# EHDD_LAB_1.net
KiCad netlist of a schematic drawn in EAGLE
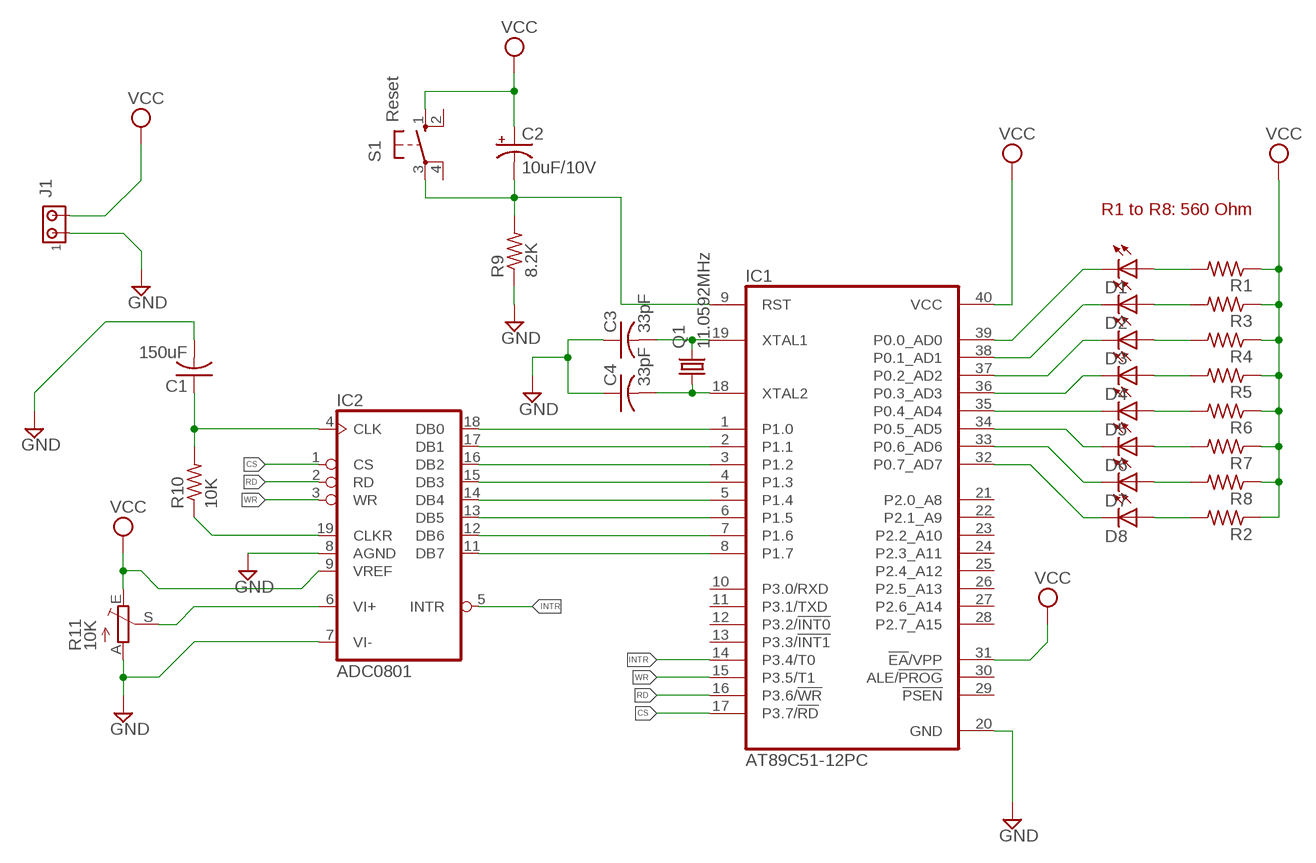
[diagram p0: schematic, sheet 1]

(export (version "E")
  (design (tool "Eeschema 10.0.6"))
  (components
    (comp (ref "C1")
      (value "150uF")
      (footprint "eagle-import:C025-025X050")
      (libsource (lib "eagle-import") (part "C-US025-025X050"))
    )
    (comp (ref "C2")
      (value "10uF/10V")
      (footprint "eagle-import:E2,5-5")
      (libsource (lib "eagle-import") (part "CPOL-USE2.5-5"))
    )
    (comp (ref "C3")
      (value "33pF")
      (footprint "eagle-import:C025-025X050")
      (libsource (lib "eagle-import") (part "C-US025-025X050"))
    )
    (comp (ref "C4")
      (value "33pF")
      (footprint "eagle-import:C025-025X050")
      (libsource (lib "eagle-import") (part "C-US025-025X050"))
    )
    (comp (ref "D1")
      (value "LEDCHIPLED_0805")
      (footprint "eagle-import:CHIPLED_0805")
      (libsource (lib "eagle-import") (part "LEDCHIPLED_0805"))
    )
    (comp (ref "D2")
      (value "LEDCHIPLED_0805")
      (footprint "eagle-import:CHIPLED_0805")
      (libsource (lib "eagle-import") (part "LEDCHIPLED_0805"))
    )
    (comp (ref "D3")
      (value "LEDCHIPLED_0805")
      (footprint "eagle-import:CHIPLED_0805")
      (libsource (lib "eagle-import") (part "LEDCHIPLED_0805"))
    )
    (comp (ref "D4")
      (value "LEDCHIPLED_0805")
      (footprint "eagle-import:CHIPLED_0805")
      (libsource (lib "eagle-import") (part "LEDCHIPLED_0805"))
    )
    (comp (ref "D5")
      (value "LEDCHIPLED_0805")
      (footprint "eagle-import:CHIPLED_0805")
      (libsource (lib "eagle-import") (part "LEDCHIPLED_0805"))
    )
    (comp (ref "D6")
      (value "LEDCHIPLED_0805")
      (footprint "eagle-import:CHIPLED_0805")
      (libsource (lib "eagle-import") (part "LEDCHIPLED_0805"))
    )
    (comp (ref "D7")
      (value "LEDCHIPLED_0805")
      (footprint "eagle-import:CHIPLED_0805")
      (libsource (lib "eagle-import") (part "LEDCHIPLED_0805"))
    )
    (comp (ref "D8")
      (value "LEDCHIPLED_0805")
      (footprint "eagle-import:CHIPLED_0805")
      (libsource (lib "eagle-import") (part "LEDCHIPLED_0805"))
    )
    (comp (ref "IC1")
      (value "AT89C51-12PC")
      (footprint "eagle-import:DIL40")
      (libsource (lib "eagle-import") (part "AT89C51-PC12"))
    )
    (comp (ref "IC2")
      (value "ADC0801")
      (footprint "eagle-import:DIL20")
      (libsource (lib "eagle-import") (part "ADC0801"))
    )
    (comp (ref "J1")
      (value "MTA02-100")
      (footprint "eagle-import:10X02MTA")
      (libsource (lib "eagle-import") (part "MTA02-100"))
    )
    (comp (ref "Q1")
      (value "11.0592MHz")
      (footprint "eagle-import:TC26H")
      (libsource (lib "eagle-import") (part "CRYSTALTC26H"))
    )
    (comp (ref "R1")
      (value "R-US_R2512")
      (footprint "eagle-import:R2512")
      (libsource (lib "eagle-import") (part "R-US_R2512"))
    )
    (comp (ref "R2")
      (value "R-US_R2512")
      (footprint "eagle-import:R2512")
      (libsource (lib "eagle-import") (part "R-US_R2512"))
    )
    (comp (ref "R3")
      (value "R-US_R2512")
      (footprint "eagle-import:R2512")
      (libsource (lib "eagle-import") (part "R-US_R2512"))
    )
    (comp (ref "R4")
      (value "R-US_R2512")
      (footprint "eagle-import:R2512")
      (libsource (lib "eagle-import") (part "R-US_R2512"))
    )
    (comp (ref "R5")
      (value "R-US_R2512")
      (footprint "eagle-import:R2512")
      (libsource (lib "eagle-import") (part "R-US_R2512"))
    )
    (comp (ref "R6")
      (value "R-US_R2512")
      (footprint "eagle-import:R2512")
      (libsource (lib "eagle-import") (part "R-US_R2512"))
    )
    (comp (ref "R7")
      (value "R-US_R2512")
      (footprint "eagle-import:R2512")
      (libsource (lib "eagle-import") (part "R-US_R2512"))
    )
    (comp (ref "R8")
      (value "R-US_R2512")
      (footprint "eagle-import:R2512")
      (libsource (lib "eagle-import") (part "R-US_R2512"))
    )
    (comp (ref "R9")
      (value "8.2K")
      (footprint "eagle-import:R2512")
      (libsource (lib "eagle-import") (part "R-US_R2512"))
    )
    (comp (ref "R10")
      (value "10K")
      (footprint "eagle-import:R2512")
      (libsource (lib "eagle-import") (part "R-US_R2512"))
    )
    (comp (ref "R11")
      (value "10K")
      (footprint "eagle-import:B25U")
      (libsource (lib "eagle-import") (part "TRIM_EU-B25U"))
    )
    (comp (ref "S1")
      (value "Reset")
      (footprint "eagle-import:B3F-10XX")
      (fields (field (name "MPN") "B3F-1000"))
      (libsource (lib "eagle-import") (part "10-XX"))
    )
  )
  (nets
    (net (code "1") (name "CS") (class "Default")
      (node (ref "IC1") (pin "17") (pinfunction "P3.7/~{RD}_17") (pintype "bidirectional"))
      (node (ref "IC2") (pin "1") (pinfunction "CS_1") (pintype "input"))
    )
    (net (code "2") (name "GND") (class "Default")
      (node (ref "C1") (pin "2") (pinfunction "2_2") (pintype "passive"))
      (node (ref "C3") (pin "1") (pinfunction "1_1") (pintype "passive"))
      (node (ref "C4") (pin "1") (pinfunction "1_1") (pintype "passive"))
      (node (ref "IC1") (pin "20") (pinfunction "GND_20") (pintype "power_in"))
      (node (ref "IC2") (pin "7") (pinfunction "VI-_7") (pintype "input"))
      (node (ref "IC2") (pin "8") (pinfunction "AGND_8") (pintype "input"))
      (node (ref "J1") (pin "1") (pinfunction "1_1") (pintype "passive"))
      (node (ref "R11") (pin "A") (pinfunction "A_A") (pintype "passive"))
      (node (ref "R9") (pin "1") (pinfunction "1_1") (pintype "passive"))
    )
    (net (code "3") (name "INTR") (class "Default")
      (node (ref "IC1") (pin "14") (pinfunction "P3.4/T0_14") (pintype "bidirectional"))
      (node (ref "IC2") (pin "5") (pinfunction "INTR_5") (pintype "output"))
    )
    (net (code "4") (name "Net-(D1-PadA)") (class "Default")
      (node (ref "D1") (pin "A") (pinfunction "A_A") (pintype "passive"))
      (node (ref "R1") (pin "2") (pinfunction "2_2") (pintype "passive"))
    )
    (net (code "5") (name "Net-(D2-PadA)") (class "Default")
      (node (ref "D2") (pin "A") (pinfunction "A_A") (pintype "passive"))
      (node (ref "R3") (pin "2") (pinfunction "2_2") (pintype "passive"))
    )
    (net (code "6") (name "Net-(D3-PadA)") (class "Default")
      (node (ref "D3") (pin "A") (pinfunction "A_A") (pintype "passive"))
      (node (ref "R4") (pin "2") (pinfunction "2_2") (pintype "passive"))
    )
    (net (code "7") (name "Net-(D4-PadA)") (class "Default")
      (node (ref "D4") (pin "A") (pinfunction "A_A") (pintype "passive"))
      (node (ref "R5") (pin "2") (pinfunction "2_2") (pintype "passive"))
    )
    (net (code "8") (name "Net-(D5-PadA)") (class "Default")
      (node (ref "D5") (pin "A") (pinfunction "A_A") (pintype "passive"))
      (node (ref "R6") (pin "2") (pinfunction "2_2") (pintype "passive"))
    )
    (net (code "9") (name "Net-(D6-PadA)") (class "Default")
      (node (ref "D6") (pin "A") (pinfunction "A_A") (pintype "passive"))
      (node (ref "R7") (pin "2") (pinfunction "2_2") (pintype "passive"))
    )
    (net (code "10") (name "Net-(D7-PadA)") (class "Default")
      (node (ref "D7") (pin "A") (pinfunction "A_A") (pintype "passive"))
      (node (ref "R8") (pin "2") (pinfunction "2_2") (pintype "passive"))
    )
    (net (code "11") (name "Net-(D8-PadA)") (class "Default")
      (node (ref "D8") (pin "A") (pinfunction "A_A") (pintype "passive"))
      (node (ref "R2") (pin "2") (pinfunction "2_2") (pintype "passive"))
    )
    (net (code "12") (name "Net-(IC1-P0.0_AD0)") (class "Default")
      (node (ref "D1") (pin "C") (pinfunction "C_C") (pintype "passive"))
      (node (ref "IC1") (pin "39") (pinfunction "P0.0_AD0_39") (pintype "bidirectional"))
    )
    (net (code "13") (name "Net-(IC1-P0.1_AD1)") (class "Default")
      (node (ref "D2") (pin "C") (pinfunction "C_C") (pintype "passive"))
      (node (ref "IC1") (pin "38") (pinfunction "P0.1_AD1_38") (pintype "bidirectional"))
    )
    (net (code "14") (name "Net-(IC1-P0.2_AD2)") (class "Default")
      (node (ref "D3") (pin "C") (pinfunction "C_C") (pintype "passive"))
      (node (ref "IC1") (pin "37") (pinfunction "P0.2_AD2_37") (pintype "bidirectional"))
    )
    (net (code "15") (name "Net-(IC1-P0.3_AD3)") (class "Default")
      (node (ref "D4") (pin "C") (pinfunction "C_C") (pintype "passive"))
      (node (ref "IC1") (pin "36") (pinfunction "P0.3_AD3_36") (pintype "bidirectional"))
    )
    (net (code "16") (name "Net-(IC1-P0.4_AD4)") (class "Default")
      (node (ref "D5") (pin "C") (pinfunction "C_C") (pintype "passive"))
      (node (ref "IC1") (pin "35") (pinfunction "P0.4_AD4_35") (pintype "bidirectional"))
    )
    (net (code "17") (name "Net-(IC1-P0.5_AD5)") (class "Default")
      (node (ref "D6") (pin "C") (pinfunction "C_C") (pintype "passive"))
      (node (ref "IC1") (pin "34") (pinfunction "P0.5_AD5_34") (pintype "bidirectional"))
    )
    (net (code "18") (name "Net-(IC1-P0.6_AD6)") (class "Default")
      (node (ref "D7") (pin "C") (pinfunction "C_C") (pintype "passive"))
      (node (ref "IC1") (pin "33") (pinfunction "P0.6_AD6_33") (pintype "bidirectional"))
    )
    (net (code "19") (name "Net-(IC1-P0.7_AD7)") (class "Default")
      (node (ref "D8") (pin "C") (pinfunction "C_C") (pintype "passive"))
      (node (ref "IC1") (pin "32") (pinfunction "P0.7_AD7_32") (pintype "bidirectional"))
    )
    (net (code "20") (name "Net-(IC1-P1.0)") (class "Default")
      (node (ref "IC1") (pin "1") (pinfunction "P1.0_1") (pintype "bidirectional"))
      (node (ref "IC2") (pin "18") (pinfunction "DB0_18") (pintype "output"))
    )
    (net (code "21") (name "Net-(IC1-P1.1)") (class "Default")
      (node (ref "IC1") (pin "2") (pinfunction "P1.1_2") (pintype "bidirectional"))
      (node (ref "IC2") (pin "17") (pinfunction "DB1_17") (pintype "output"))
    )
    (net (code "22") (name "Net-(IC1-P1.2)") (class "Default")
      (node (ref "IC1") (pin "3") (pinfunction "P1.2_3") (pintype "bidirectional"))
      (node (ref "IC2") (pin "16") (pinfunction "DB2_16") (pintype "output"))
    )
    (net (code "23") (name "Net-(IC1-P1.3)") (class "Default")
      (node (ref "IC1") (pin "4") (pinfunction "P1.3_4") (pintype "bidirectional"))
      (node (ref "IC2") (pin "15") (pinfunction "DB3_15") (pintype "output"))
    )
    (net (code "24") (name "Net-(IC1-P1.4)") (class "Default")
      (node (ref "IC1") (pin "5") (pinfunction "P1.4_5") (pintype "bidirectional"))
      (node (ref "IC2") (pin "14") (pinfunction "DB4_14") (pintype "output"))
    )
    (net (code "25") (name "Net-(IC1-P1.5)") (class "Default")
      (node (ref "IC1") (pin "6") (pinfunction "P1.5_6") (pintype "bidirectional"))
      (node (ref "IC2") (pin "13") (pinfunction "DB5_13") (pintype "output"))
    )
    (net (code "26") (name "Net-(IC1-P1.6)") (class "Default")
      (node (ref "IC1") (pin "7") (pinfunction "P1.6_7") (pintype "bidirectional"))
      (node (ref "IC2") (pin "12") (pinfunction "DB6_12") (pintype "output"))
    )
    (net (code "27") (name "Net-(IC1-P1.7)") (class "Default")
      (node (ref "IC1") (pin "8") (pinfunction "P1.7_8") (pintype "bidirectional"))
      (node (ref "IC2") (pin "11") (pinfunction "DB7_11") (pintype "output"))
    )
    (net (code "28") (name "Net-(IC1-RST)") (class "Default")
      (node (ref "C2") (pin "-") (pinfunction "-_-") (pintype "passive"))
      (node (ref "IC1") (pin "9") (pinfunction "RST_9") (pintype "input"))
      (node (ref "R9") (pin "2") (pinfunction "2_2") (pintype "passive"))
      (node (ref "S1") (pin "3") (pinfunction "P_3") (pintype "passive"))
    )
    (net (code "29") (name "Net-(IC1-XTAL1)") (class "Default")
      (node (ref "C3") (pin "2") (pinfunction "2_2") (pintype "passive"))
      (node (ref "IC1") (pin "19") (pinfunction "XTAL1_19") (pintype "input"))
      (node (ref "Q1") (pin "2") (pinfunction "2_2") (pintype "passive"))
    )
    (net (code "30") (name "Net-(IC1-XTAL2)") (class "Default")
      (node (ref "C4") (pin "2") (pinfunction "2_2") (pintype "passive"))
      (node (ref "IC1") (pin "18") (pinfunction "XTAL2_18") (pintype "input"))
      (node (ref "Q1") (pin "1") (pinfunction "1_1") (pintype "passive"))
    )
    (net (code "31") (name "Net-(IC2A-CLK)") (class "Default")
      (node (ref "C1") (pin "1") (pinfunction "1_1") (pintype "passive"))
      (node (ref "IC2") (pin "4") (pinfunction "CLK_4") (pintype "input"))
      (node (ref "R10") (pin "2") (pinfunction "2_2") (pintype "passive"))
    )
    (net (code "32") (name "Net-(IC2A-CLKR)") (class "Default")
      (node (ref "IC2") (pin "19") (pinfunction "CLKR_19") (pintype "input"))
      (node (ref "R10") (pin "1") (pinfunction "1_1") (pintype "passive"))
    )
    (net (code "33") (name "Net-(IC2A-VI+)") (class "Default")
      (node (ref "IC2") (pin "6") (pinfunction "VI+_6") (pintype "input"))
      (node (ref "R11") (pin "S") (pinfunction "S_S") (pintype "passive"))
    )
    (net (code "34") (name "RD") (class "Default")
      (node (ref "IC1") (pin "16") (pinfunction "P3.6/~{WR}_16") (pintype "bidirectional"))
      (node (ref "IC2") (pin "2") (pinfunction "RD_2") (pintype "input"))
    )
    (net (code "35") (name "VCC") (class "Default")
      (node (ref "C2") (pin "+") (pinfunction "+_+") (pintype "passive"))
      (node (ref "IC1") (pin "31") (pinfunction "~{EA}/VPP_31") (pintype "input"))
      (node (ref "IC1") (pin "40") (pinfunction "VCC_40") (pintype "power_in"))
      (node (ref "IC2") (pin "9") (pinfunction "VREF_9") (pintype "input"))
      (node (ref "J1") (pin "2") (pinfunction "2_2") (pintype "passive"))
      (node (ref "R1") (pin "1") (pinfunction "1_1") (pintype "passive"))
      (node (ref "R11") (pin "E") (pinfunction "E_E") (pintype "passive"))
      (node (ref "R2") (pin "1") (pinfunction "1_1") (pintype "passive"))
      (node (ref "R3") (pin "1") (pinfunction "1_1") (pintype "passive"))
      (node (ref "R4") (pin "1") (pinfunction "1_1") (pintype "passive"))
      (node (ref "R5") (pin "1") (pinfunction "1_1") (pintype "passive"))
      (node (ref "R6") (pin "1") (pinfunction "1_1") (pintype "passive"))
      (node (ref "R7") (pin "1") (pinfunction "1_1") (pintype "passive"))
      (node (ref "R8") (pin "1") (pinfunction "1_1") (pintype "passive"))
      (node (ref "S1") (pin "1") (pinfunction "S_1") (pintype "passive"))
    )
    (net (code "36") (name "WR") (class "Default")
      (node (ref "IC1") (pin "15") (pinfunction "P3.5/T1_15") (pintype "bidirectional"))
      (node (ref "IC2") (pin "3") (pinfunction "WR_3") (pintype "input"))
    )
    (net (code "37") (name "unconnected-(IC1-ALE{slash}~{PROG}-Pad30)") (class "Default")
      (node (ref "IC1") (pin "30") (pinfunction "ALE/~{PROG}_30") (pintype "output"))
    )
    (net (code "38") (name "unconnected-(IC1-P2.0_A8-Pad21)") (class "Default")
      (node (ref "IC1") (pin "21") (pinfunction "P2.0_A8_21") (pintype "bidirectional"))
    )
    (net (code "39") (name "unconnected-(IC1-P2.1_A9-Pad22)") (class "Default")
      (node (ref "IC1") (pin "22") (pinfunction "P2.1_A9_22") (pintype "bidirectional"))
    )
    (net (code "40") (name "unconnected-(IC1-P2.2_A10-Pad23)") (class "Default")
      (node (ref "IC1") (pin "23") (pinfunction "P2.2_A10_23") (pintype "bidirectional"))
    )
    (net (code "41") (name "unconnected-(IC1-P2.3_A11-Pad24)") (class "Default")
      (node (ref "IC1") (pin "24") (pinfunction "P2.3_A11_24") (pintype "bidirectional"))
    )
    (net (code "42") (name "unconnected-(IC1-P2.4_A12-Pad25)") (class "Default")
      (node (ref "IC1") (pin "25") (pinfunction "P2.4_A12_25") (pintype "bidirectional"))
    )
    (net (code "43") (name "unconnected-(IC1-P2.5_A13-Pad26)") (class "Default")
      (node (ref "IC1") (pin "26") (pinfunction "P2.5_A13_26") (pintype "bidirectional"))
    )
    (net (code "44") (name "unconnected-(IC1-P2.6_A14-Pad27)") (class "Default")
      (node (ref "IC1") (pin "27") (pinfunction "P2.6_A14_27") (pintype "bidirectional"))
    )
    (net (code "45") (name "unconnected-(IC1-P2.7_A15-Pad28)") (class "Default")
      (node (ref "IC1") (pin "28") (pinfunction "P2.7_A15_28") (pintype "bidirectional"))
    )
    (net (code "46") (name "unconnected-(IC1-P3.0{slash}RXD-Pad10)") (class "Default")
      (node (ref "IC1") (pin "10") (pinfunction "P3.0/RXD_10") (pintype "bidirectional"))
    )
    (net (code "47") (name "unconnected-(IC1-P3.1{slash}TXD-Pad11)") (class "Default")
      (node (ref "IC1") (pin "11") (pinfunction "P3.1/TXD_11") (pintype "bidirectional"))
    )
    (net (code "48") (name "unconnected-(IC1-P3.2{slash}~{INT0}-Pad12)") (class "Default")
      (node (ref "IC1") (pin "12") (pinfunction "P3.2/~{INT0}_12") (pintype "bidirectional"))
    )
    (net (code "49") (name "unconnected-(IC1-P3.3{slash}~{INT1}-Pad13)") (class "Default")
      (node (ref "IC1") (pin "13") (pinfunction "P3.3/~{INT1}_13") (pintype "bidirectional"))
    )
    (net (code "50") (name "unconnected-(IC1-~{PSEN}-Pad29)") (class "Default")
      (node (ref "IC1") (pin "29") (pinfunction "~{PSEN}_29") (pintype "output"))
    )
    (net (code "51") (name "unconnected-(S1-P1-Pad4)") (class "Default")
      (node (ref "S1") (pin "4") (pinfunction "P1_4") (pintype "passive"))
    )
    (net (code "52") (name "unconnected-(S1-S1-Pad2)") (class "Default")
      (node (ref "S1") (pin "2") (pinfunction "S1_2") (pintype "passive"))
    )
  )
)
